# MCU.net
KiCad netlist of a schematic drawn in Altium Designer
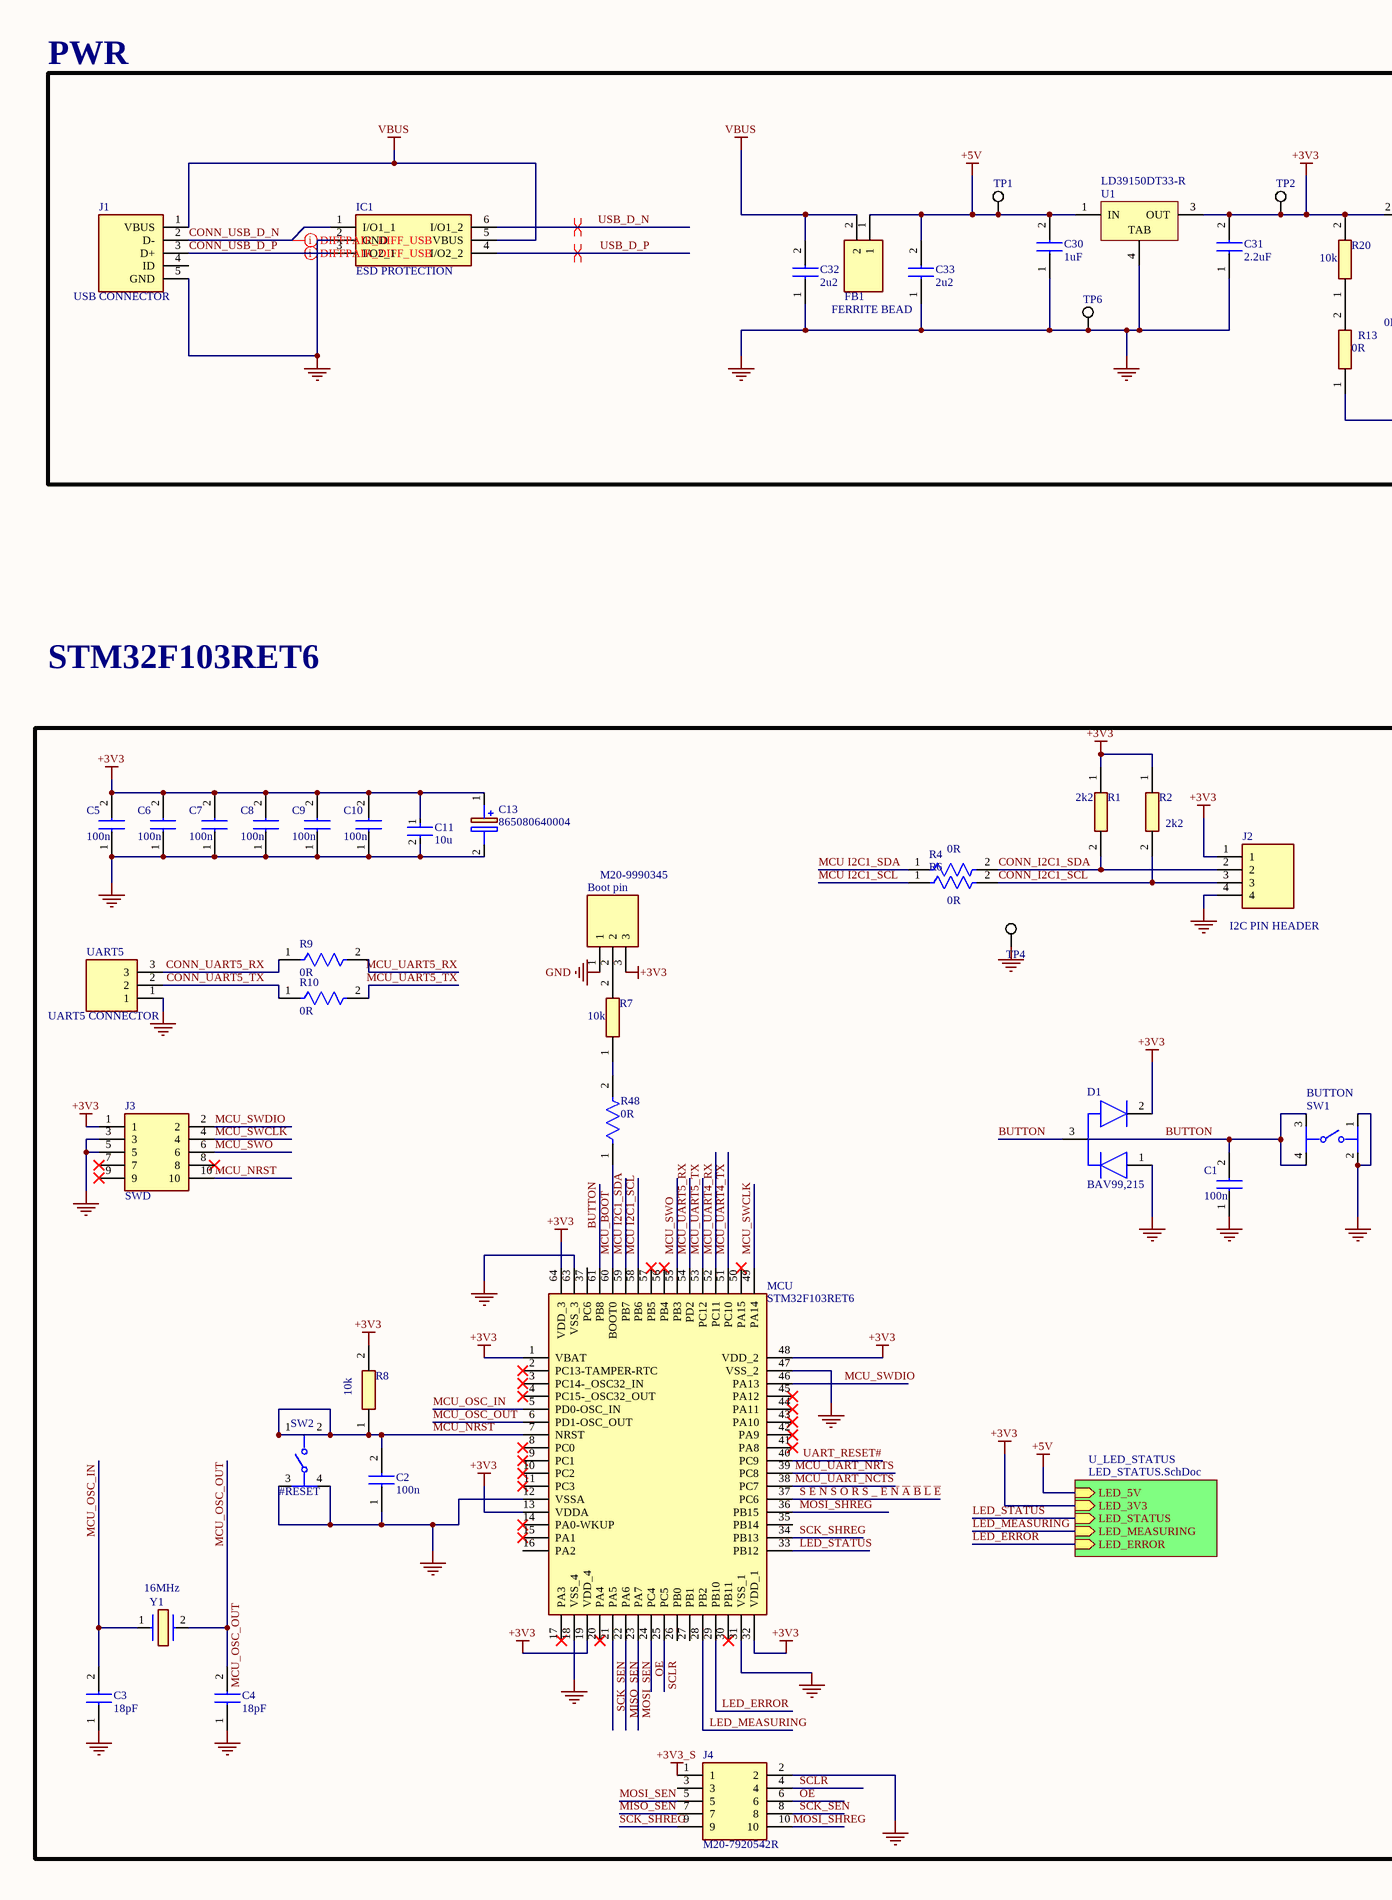
[diagram p0: MCU.SchDoc, left]
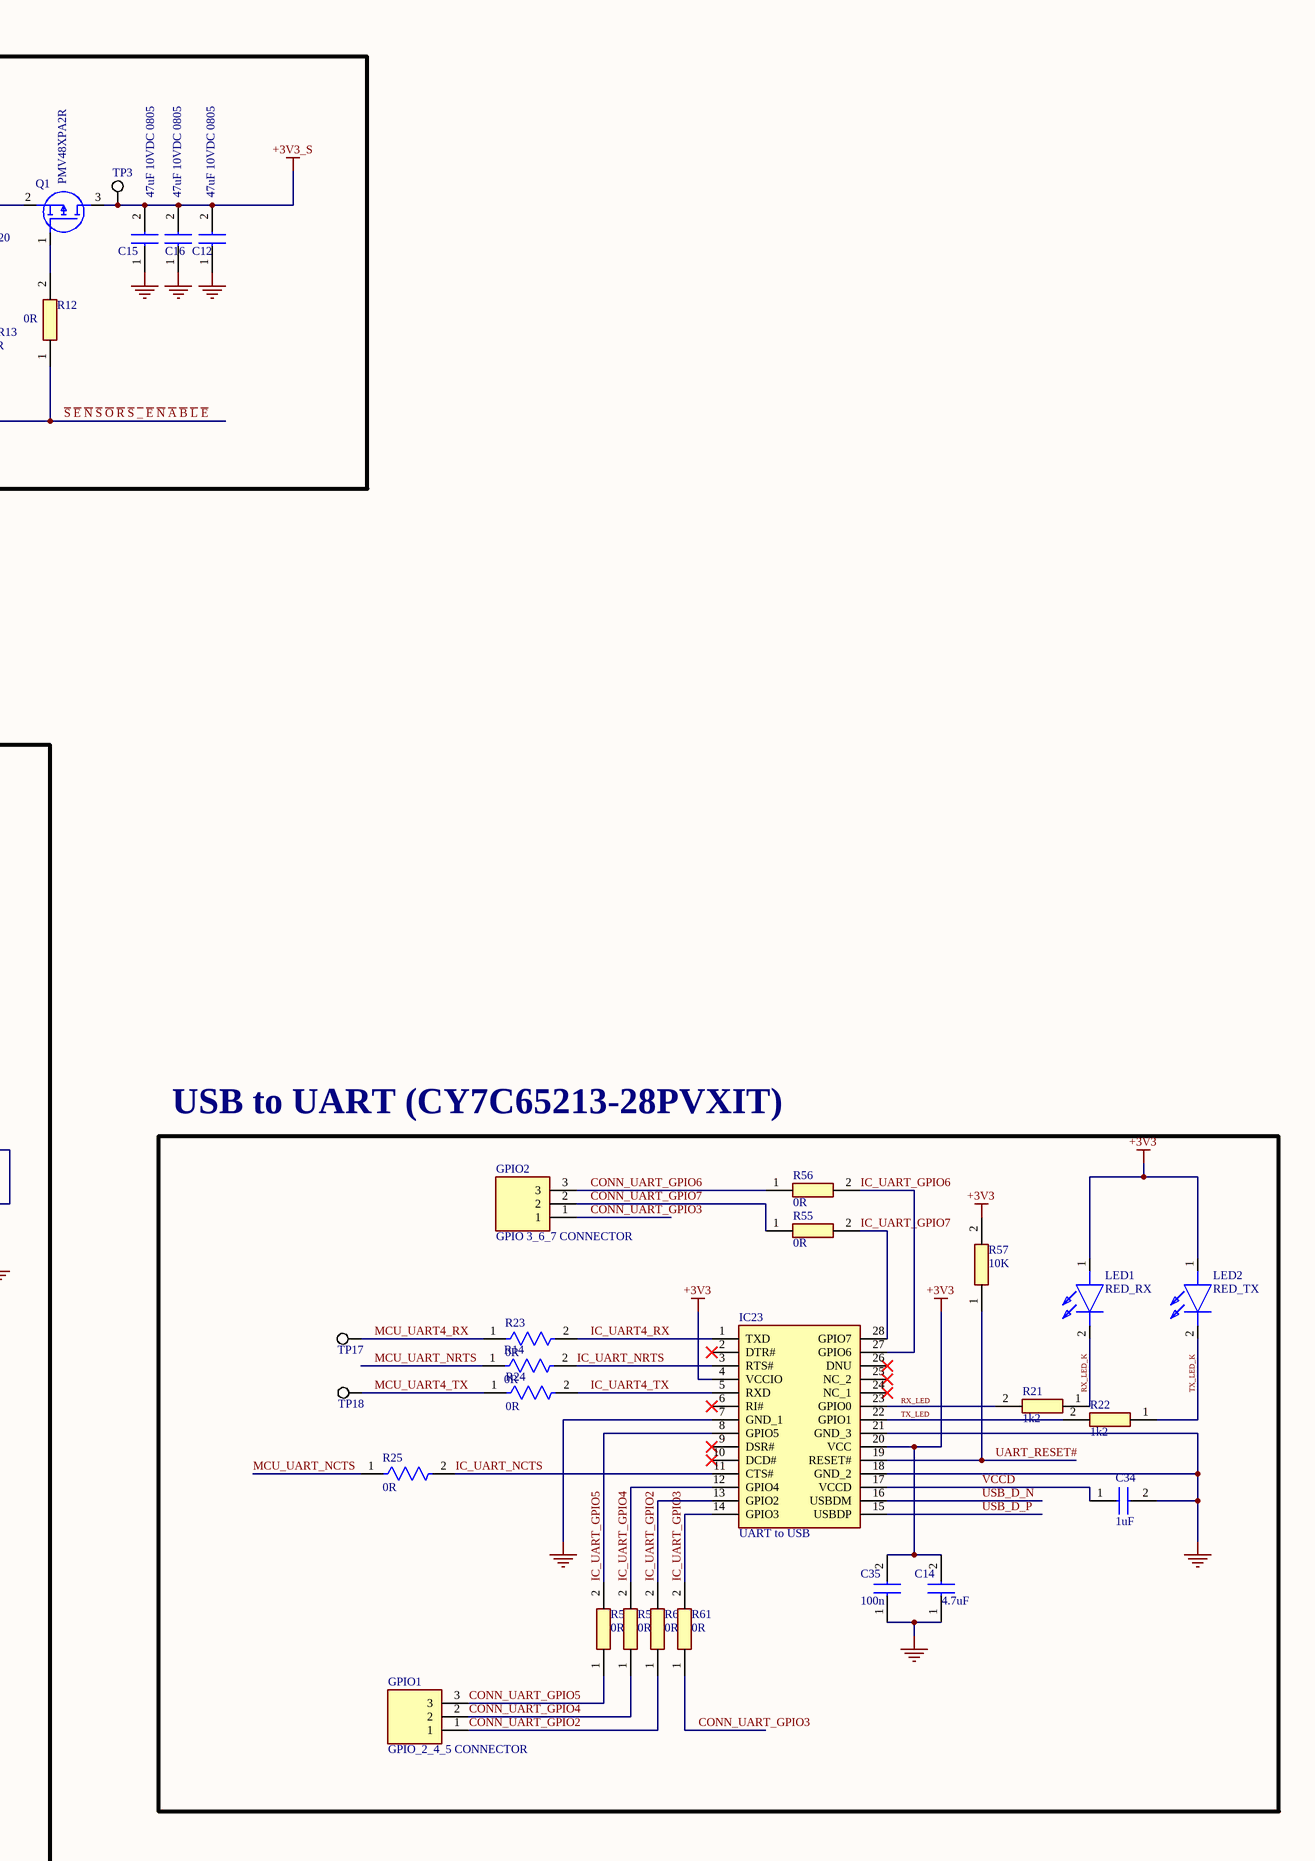
[diagram p1: MCU.SchDoc, right]

(export (version "E")
  (design (tool "Eeschema 10.0.6"))
  (components
    (comp (ref "Boot pin")
      (value "M20-9990345")
      (footprint "SamacSys:HDRV3W64P0X254_1X3_762X254X864P")
      (description "Connector")
      (fields (field (name "MOUSER PART NUMBER") "855-M20-9990345"))
      (libsource (lib "SamacSys") (part "M20-9990345"))
    )
    (comp (ref "C1")
      (value "100n")
      (footprint "SamacSys:CAPC1608X95N")
      (description "Capacitor")
      (fields
        (field (name "MANUFACTURER_PART_NUMBER") "C0603C104J4RAC")
        (field (name "MOUSER PART NUMBER") "80-C0603C104J4RAC")
      )
      (libsource (lib "SamacSys") (part "C0603C104J4RAC"))
    )
    (comp (ref "C2")
      (value "100n")
      (footprint "SamacSys:CAPC1608X90N")
      (description "Capacitor")
      (fields
        (field (name "MANUFACTURER_PART_NUMBER") "CL10A105KA8NFNC")
        (field (name "MOUSER PART NUMBER") "187-CL10A105KA8NFNC")
      )
      (libsource (lib "*") (part "CL10A105KA8NFNC"))
    )
    (comp (ref "C3")
      (value "18pF")
      (footprint "SamacSys:C0603")
      (description "Capacitor")
      (fields
        (field (name "MANUFACTURER_PART_NUMBER") "C0603C180K4HACTU")
        (field (name "MOUSER PART NUMBER") "80-C0603C180K4HACTU")
      )
      (libsource (lib "*") (part "C0603C180K4HACTU"))
    )
    (comp (ref "C4")
      (value "18pF")
      (footprint "SamacSys:C0603")
      (description "Capacitor")
      (fields
        (field (name "MANUFACTURER_PART_NUMBER") "C0603C180K4HACTU")
        (field (name "MOUSER PART NUMBER") "80-C0603C180K4HACTU")
      )
      (libsource (lib "*") (part "C0603C180K4HACTU"))
    )
    (comp (ref "C5")
      (value "100n")
      (footprint "SamacSys:CAPC1608X95N")
      (description "Capacitor")
      (fields
        (field (name "MANUFACTURER_PART_NUMBER") "C0603C104J4RAC")
        (field (name "MOUSER PART NUMBER") "80-C0603C104J4RAC")
      )
      (libsource (lib "SamacSys") (part "C0603C104J4RAC"))
    )
    (comp (ref "C6")
      (value "100n")
      (footprint "SamacSys:CAPC1608X95N")
      (description "Capacitor")
      (fields
        (field (name "MANUFACTURER_PART_NUMBER") "C0603C104J4RAC")
        (field (name "MOUSER PART NUMBER") "80-C0603C104J4RAC")
      )
      (libsource (lib "SamacSys") (part "C0603C104J4RAC"))
    )
    (comp (ref "C7")
      (value "100n")
      (footprint "SamacSys:CAPC1608X95N")
      (description "Capacitor")
      (fields
        (field (name "MANUFACTURER_PART_NUMBER") "C0603C104J4RAC")
        (field (name "MOUSER PART NUMBER") "80-C0603C104J4RAC")
      )
      (libsource (lib "SamacSys") (part "C0603C104J4RAC"))
    )
    (comp (ref "C8")
      (value "100n")
      (footprint "SamacSys:CAPC1608X95N")
      (description "Capacitor")
      (fields
        (field (name "MANUFACTURER_PART_NUMBER") "C0603C104J4RAC")
        (field (name "MOUSER PART NUMBER") "80-C0603C104J4RAC")
      )
      (libsource (lib "SamacSys") (part "C0603C104J4RAC"))
    )
    (comp (ref "C9")
      (value "100n")
      (footprint "SamacSys:CAPC1608X95N")
      (description "Capacitor")
      (fields
        (field (name "MANUFACTURER_PART_NUMBER") "C0603C104J4RAC")
        (field (name "MOUSER PART NUMBER") "80-C0603C104J4RAC")
      )
      (libsource (lib "SamacSys") (part "C0603C104J4RAC"))
    )
    (comp (ref "C10")
      (value "100n")
      (footprint "SamacSys:CAPC1608X95N")
      (description "Capacitor")
      (fields
        (field (name "MANUFACTURER_PART_NUMBER") "C0603C104J4RAC")
        (field (name "MOUSER PART NUMBER") "80-C0603C104J4RAC")
      )
      (libsource (lib "SamacSys") (part "C0603C104J4RAC"))
    )
    (comp (ref "C11")
      (value "10u")
      (footprint "FP-GRM188-0_2-IPC_A")
      (description "Chip Multilayer Ceramic Capacitors for General Purpose, 0603, 10uF, X5R, 15%, 20%, 16V")
      (fields (field (name "TOLERANCE") "20%") (field (name "VOLTAGE") "16V"))
      (libsource (lib "Altium Content Vault") (part "11868f565c42a9108669ba33697ecf6"))
    )
    (comp (ref "C12")
      (value "47uF 10VDC 0805")
      (footprint "SamacSys:CAPC2012X145N")
      (description "Capacitor")
      (fields
        (field (name "MANUFACTURER_PART_NUMBER") "GRM21BR61A476ME15K")
        (field (name "MOUSER PART NUMBER") "81-GRM21BR61A476ME5K")
      )
      (libsource (lib "*") (part "GRM21BR61A476ME15K"))
    )
    (comp (ref "C13")
      (value "865080640004")
      (footprint "SamacSys:865080640004")
      (description "Capacitor Polarised")
      (fields (field (name "MOUSER PART NUMBER") "710-865080640004"))
      (libsource (lib "SamacSys") (part "865080640004"))
    )
    (comp (ref "C14")
      (value "4.7uF")
      (footprint "SamacSys:CAPC1608X95N")
      (description "Capacitor")
      (fields
        (field (name "MANUFACTURER_PART_NUMBER") "C0603C104J4RAC")
        (field (name "MOUSER PART NUMBER") "80-C0603C104J4RAC")
      )
      (libsource (lib "SamacSys") (part "C0603C104J4RAC"))
    )
    (comp (ref "C15")
      (value "47uF 10VDC 0805")
      (footprint "SamacSys:CAPC2012X145N")
      (description "Capacitor")
      (fields
        (field (name "MANUFACTURER_PART_NUMBER") "GRM21BR61A476ME15K")
        (field (name "MOUSER PART NUMBER") "81-GRM21BR61A476ME5K")
      )
      (libsource (lib "*") (part "GRM21BR61A476ME15K"))
    )
    (comp (ref "C16")
      (value "47uF 10VDC 0805")
      (footprint "SamacSys:CAPC2012X145N")
      (description "Capacitor")
      (fields
        (field (name "MANUFACTURER_PART_NUMBER") "GRM21BR61A476ME15K")
        (field (name "MOUSER PART NUMBER") "81-GRM21BR61A476ME5K")
      )
      (libsource (lib "*") (part "GRM21BR61A476ME15K"))
    )
    (comp (ref "C30")
      (value "1uF")
      (footprint "SamacSys:CAPC1608X90N")
      (description "Capacitor")
      (fields
        (field (name "MANUFACTURER_PART_NUMBER") "CL10A105KA8NFNC")
        (field (name "MOUSER PART NUMBER") "187-CL10A105KA8NFNC")
      )
      (libsource (lib "*") (part "CL10A105KA8NFNC"))
    )
    (comp (ref "C31")
      (value "2.2uF")
      (footprint "SamacSys:CAPC1608X90N")
      (description "Capacitor")
      (fields
        (field (name "MANUFACTURER_PART_NUMBER") "CL10A105KA8NFNC")
        (field (name "MOUSER PART NUMBER") "187-CL10A105KA8NFNC")
      )
      (libsource (lib "*") (part "CL10A105KA8NFNC"))
    )
    (comp (ref "C32")
      (value "2u2")
      (footprint "SamacSys:CAPC1608X90N")
      (description "Capacitor")
      (fields
        (field (name "MANUFACTURER_PART_NUMBER") "CL10A105KA8NFNC")
        (field (name "MOUSER PART NUMBER") "187-CL10A105KA8NFNC")
      )
      (libsource (lib "*") (part "CL10A105KA8NFNC"))
    )
    (comp (ref "C33")
      (value "2u2")
      (footprint "SamacSys:CAPC1608X90N")
      (description "Capacitor")
      (fields
        (field (name "MANUFACTURER_PART_NUMBER") "CL10A105KA8NFNC")
        (field (name "MOUSER PART NUMBER") "187-CL10A105KA8NFNC")
      )
      (libsource (lib "*") (part "CL10A105KA8NFNC"))
    )
    (comp (ref "C34")
      (value "1uF")
      (footprint "SamacSys:CAPC1608X90N")
      (description "Capacitor")
      (fields
        (field (name "MANUFACTURER_PART_NUMBER") "CL10A105KA8NFNC")
        (field (name "MOUSER PART NUMBER") "187-CL10A105KA8NFNC")
      )
      (libsource (lib "SamacSys") (part "CL10A105KA8NFNC"))
    )
    (comp (ref "C35")
      (value "100n")
      (footprint "SamacSys:CAPC1608X95N")
      (description "Capacitor")
      (fields
        (field (name "MANUFACTURER_PART_NUMBER") "C0603C104J4RAC")
        (field (name "MOUSER PART NUMBER") "80-C0603C104J4RAC")
      )
      (libsource (lib "SamacSys") (part "C0603C104J4RAC"))
    )
    (comp (ref "D1")
      (value "BAV99,215")
      (footprint "SamacSys:BAV99215")
      (description "Diode")
      (fields (field (name "MOUSER PART NUMBER") "771-BAV99-T/R"))
      (libsource (lib "*") (part "BAV99,215"))
    )
    (comp (ref "FB1")
      (value "FERRITE BEAD")
      (footprint "SamacSys:BEADC1608X75N")
      (description "Ferrite Bead")
      (fields
        (field (name "MANUFACTURER_PART_NUMBER") "BLM18KN101EH1D")
        (field (name "MOUSER PART NUMBER") "81-BLM18KN101EH1D")
      )
      (libsource (lib "SamacSys") (part "BLM18KN101EH1D"))
    )
    (comp (ref "GPIO1")
      (value "GPIO_2_4_5 CONNECTOR")
      (footprint "SamacSys:HDRV3W64P0X254_1X3_762X254X864P")
      (description "Connector")
      (fields
        (field (name "MANUFACTURER_PART_NUMBER") "M20-9990345")
        (field (name "MOUSER PART NUMBER") "855-M20-9990345")
      )
      (libsource (lib "") (part "M20-9990345_1"))
    )
    (comp (ref "GPIO2")
      (value "GPIO 3_6_7 CONNECTOR")
      (footprint "SamacSys:HDRV3W64P0X254_1X3_762X254X864P")
      (description "Connector")
      (fields
        (field (name "MANUFACTURER_PART_NUMBER") "M20-9990345")
        (field (name "MOUSER PART NUMBER") "855-M20-9990345")
      )
      (libsource (lib "") (part "M20-9990345_1"))
    )
    (comp (ref "IC1")
      (value "ESD PROTECTION")
      (footprint "SamacSys:SOT95P280X145-6N")
      (description "Integrated Circuit")
      (fields
        (field (name "MANUFACTURER_PART_NUMBER") "USBLC6-2SC6")
        (field (name "MOUSER PART NUMBER") "511-USBLC6-2SC6")
      )
      (libsource (lib "*") (part "USBLC6-2SC6"))
    )
    (comp (ref "IC23")
      (value "UART to USB")
      (footprint "SamacSys:SOP65P780X200-28N")
      (description "Integrated Circuit")
      (fields
        (field (name "MANUFACTURER_PART_NUMBER") "CY7C65213-28PVXIT")
        (field (name "MOUSER PART NUMBER") "727-CY7C6521328PVXIT")
      )
      (libsource (lib "*") (part "CY7C65213-28PVXIT"))
    )
    (comp (ref "J1")
      (value "USB CONNECTOR")
      (footprint "SamacSys:47346-0001")
      (description "Connector")
      (fields
        (field (name "MANUFACTURER_PART_NUMBER") "47346-0001")
        (field (name "MOUSER PART NUMBER") "538-47346-0001")
      )
      (libsource (lib "*") (part "47346-0001"))
    )
    (comp (ref "J2")
      (value "I2C PIN HEADER")
      (footprint "SamacSys:HDRV4W90P0X254_1X4_994X249X560P")
      (description "Connector")
      (fields
        (field (name "MANUFACTURER_PART_NUMBER") "90120-0764")
        (field (name "MOUSER PART NUMBER") "538-90120-0764")
      )
      (libsource (lib "SamacSys") (part "90120-0764"))
    )
    (comp (ref "J3")
      (value "SWD")
      (footprint "SamacSys:HDRV10W64P254_2X5_1270X508X834P")
      (description "Connector")
      (fields
        (field (name "MANUFACTURER_PART_NUMBER") "M20-9760542")
        (field (name "MOUSER PART NUMBER") "855-M20-9760542")
      )
      (libsource (lib "SamacSys") (part "M20-9760542"))
    )
    (comp (ref "J4")
      (value "M20-7920542R")
      (footprint "SamacSys:M207920542R")
      (description "Connector")
      (fields (field (name "MOUSER PART NUMBER") "855-M20-7920542R"))
      (libsource (lib "SamacSys") (part "M20-7920542R"))
    )
    (comp (ref "LED1")
      (value "RED_RX")
      (footprint "SamacSys:APT2012SECKJ3PRV")
      (description "LED")
      (fields
        (field (name "MANUFACTURER_PART_NUMBER") "APT2012SECK/J3-PRV")
        (field (name "MOUSER PART NUMBER") "604-APT2012SECKJ3PRV")
      )
      (libsource (lib "*") (part "APT2012SECK_J3-PRV"))
    )
    (comp (ref "LED2")
      (value "RED_TX")
      (footprint "SamacSys:APT2012SECKJ3PRV")
      (description "LED")
      (fields
        (field (name "MANUFACTURER_PART_NUMBER") "APT2012SECK/J3-PRV")
        (field (name "MOUSER PART NUMBER") "604-APT2012SECKJ3PRV")
      )
      (libsource (lib "*") (part "APT2012SECK_J3-PRV"))
    )
    (comp (ref "MCU")
      (value "STM32F103RET6")
      (footprint "SamacSys:QFP50P1200X1200X160-64N")
      (description "Integrated Circuit")
      (fields (field (name "MOUSER PART NUMBER") "511-STM32F103RET6"))
      (libsource (lib "*") (part "STM32F103RET6"))
    )
    (comp (ref "Q1")
      (value "PMV48XPA2R")
      (footprint "SamacSys:SOT95P230X110-3N")
      (description "MOSFET (P-Channel)")
      (fields (field (name "MOUSER PART NUMBER") "771-PMV48XPA2R"))
      (libsource (lib "*") (part "PMV48XPA2R"))
    )
    (comp (ref "R1")
      (value "2k2")
      (footprint "SamacSys:RESC1608X55N")
      (description "Resistor")
      (fields
        (field (name "MANUFACTURER_PART_NUMBER") "RK73B1JTTD103J")
        (field (name "MOUSER PART NUMBER") "660-RK73B1JTTD103J")
      )
      (libsource (lib "") (part "RK73B1JTTD103J_2"))
    )
    (comp (ref "R2")
      (value "2k2")
      (footprint "SamacSys:RESC1608X55N")
      (description "Resistor")
      (fields
        (field (name "MANUFACTURER_PART_NUMBER") "RK73B1JTTD103J")
        (field (name "MOUSER PART NUMBER") "660-RK73B1JTTD103J")
      )
      (libsource (lib "") (part "RK73B1JTTD103J_2"))
    )
    (comp (ref "R4")
      (value "0R")
      (footprint "FP-ERJ-3GEY0R00V-MFG")
      (description "RES SMD 0 OHM JUMPER 1/10W 0603")
      (fields (field (name "TOLERANCE") "5%") (field (name "MANUFACTURER PART NUMBER") "ERJ-3GEY0R00V"))
      (libsource (lib "Altium Content Vault") (part "1029c3af85768c4190bb7ad29bc67b5"))
    )
    (comp (ref "R6")
      (value "0R")
      (footprint "FP-ERJ-3GEY0R00V-MFG")
      (description "RES SMD 0 OHM JUMPER 1/10W 0603")
      (fields (field (name "TOLERANCE") "5%") (field (name "MANUFACTURER PART NUMBER") "ERJ-3GEY0R00V"))
      (libsource (lib "Altium Content Vault") (part "1029c3af85768c4190bb7ad29bc67b5"))
    )
    (comp (ref "R7")
      (value "10k")
      (footprint "SamacSys:RESC1608X55N")
      (description "Resistor")
      (fields
        (field (name "MANUFACTURER_PART_NUMBER") "RK73B1JTTD103J")
        (field (name "MOUSER PART NUMBER") "660-RK73B1JTTD103J")
      )
      (libsource (lib "*") (part "RK73B1JTTD103J"))
    )
    (comp (ref "R8")
      (value "10k")
      (footprint "SamacSys:RESC1608X55N")
      (description "Resistor")
      (fields
        (field (name "MANUFACTURER_PART_NUMBER") "RK73B1JTTD103J")
        (field (name "MOUSER PART NUMBER") "660-RK73B1JTTD103J")
      )
      (libsource (lib "*") (part "RK73B1JTTD103J"))
    )
    (comp (ref "R9")
      (value "0R")
      (footprint "FP-ERJ-3GEY0R00V-MFG")
      (description "RES SMD 0 OHM JUMPER 1/10W 0603")
      (fields (field (name "TOLERANCE") "5%") (field (name "MANUFACTURER PART NUMBER") "ERJ-3GEY0R00V"))
      (libsource (lib "Altium Content Vault") (part "1029c3af85768c4190bb7ad29bc67b5"))
    )
    (comp (ref "R10")
      (value "0R")
      (footprint "FP-ERJ-3GEY0R00V-MFG")
      (description "RES SMD 0 OHM JUMPER 1/10W 0603")
      (fields (field (name "TOLERANCE") "5%") (field (name "MANUFACTURER PART NUMBER") "ERJ-3GEY0R00V"))
      (libsource (lib "Altium Content Vault") (part "1029c3af85768c4190bb7ad29bc67b5"))
    )
    (comp (ref "R12")
      (value "0R")
      (footprint "SamacSys:RESC1608X55N")
      (description "Resistor")
      (fields
        (field (name "MANUFACTURER_PART_NUMBER") "RK73B1JTTD103J")
        (field (name "MOUSER PART NUMBER") "660-RK73B1JTTD103J")
      )
      (libsource (lib "*") (part "RK73B1JTTD103J"))
    )
    (comp (ref "R13")
      (value "0R")
      (footprint "SamacSys:RESC1608X55N")
      (description "Resistor")
      (fields
        (field (name "MANUFACTURER_PART_NUMBER") "RK73B1JTTD103J")
        (field (name "MOUSER PART NUMBER") "660-RK73B1JTTD103J")
      )
      (libsource (lib "*") (part "RK73B1JTTD103J"))
    )
    (comp (ref "R14")
      (value "0R")
      (footprint "FP-ERJ-3GEY0R00V-MFG")
      (description "RES SMD 0 OHM JUMPER 1/10W 0603")
      (fields (field (name "TOLERANCE") "5%") (field (name "MANUFACTURER PART NUMBER") "ERJ-3GEY0R00V"))
      (libsource (lib "Altium Content Vault") (part "1029c3af85768c4190bb7ad29bc67b5"))
    )
    (comp (ref "R20")
      (value "10k")
      (footprint "SamacSys:RESC1608X55N")
      (description "Resistor")
      (fields
        (field (name "MANUFACTURER_PART_NUMBER") "RK73B1JTTD103J")
        (field (name "MOUSER PART NUMBER") "660-RK73B1JTTD103J")
      )
      (libsource (lib "*") (part "RK73B1JTTD103J"))
    )
    (comp (ref "R21")
      (value "1k2")
      (footprint "SamacSys:RESC1608X55N")
      (description "Resistor")
      (fields
        (field (name "MANUFACTURER_PART_NUMBER") "RK73B1JTTD103J")
        (field (name "MOUSER PART NUMBER") "660-RK73B1JTTD103J")
      )
      (libsource (lib "") (part "RK73B1JTTD103J_3"))
    )
    (comp (ref "R22")
      (value "1k2")
      (footprint "SamacSys:RESC1608X55N")
      (description "Resistor")
      (fields
        (field (name "MANUFACTURER_PART_NUMBER") "RK73B1JTTD103J")
        (field (name "MOUSER PART NUMBER") "660-RK73B1JTTD103J")
      )
      (libsource (lib "") (part "RK73B1JTTD103J_3"))
    )
    (comp (ref "R23")
      (value "0R")
      (footprint "FP-ERJ-3GEY0R00V-MFG")
      (description "RES SMD 0 OHM JUMPER 1/10W 0603")
      (fields (field (name "TOLERANCE") "5%") (field (name "MANUFACTURER PART NUMBER") "ERJ-3GEY0R00V"))
      (libsource (lib "Altium Content Vault") (part "1029c3af85768c4190bb7ad29bc67b5"))
    )
    (comp (ref "R24")
      (value "0R")
      (footprint "FP-ERJ-3GEY0R00V-MFG")
      (description "RES SMD 0 OHM JUMPER 1/10W 0603")
      (fields (field (name "TOLERANCE") "5%") (field (name "MANUFACTURER PART NUMBER") "ERJ-3GEY0R00V"))
      (libsource (lib "Altium Content Vault") (part "1029c3af85768c4190bb7ad29bc67b5"))
    )
    (comp (ref "R25")
      (value "0R")
      (footprint "FP-ERJ-3GEY0R00V-MFG")
      (description "RES SMD 0 OHM JUMPER 1/10W 0603")
      (fields (field (name "TOLERANCE") "5%") (field (name "MANUFACTURER PART NUMBER") "ERJ-3GEY0R00V"))
      (libsource (lib "Altium Content Vault") (part "1029c3af85768c4190bb7ad29bc67b5"))
    )
    (comp (ref "R48")
      (value "0R")
      (footprint "FP-ERJ-3GEY0R00V-MFG")
      (description "RES SMD 0 OHM JUMPER 1/10W 0603")
      (fields (field (name "TOLERANCE") "5%") (field (name "MANUFACTURER PART NUMBER") "ERJ-3GEY0R00V"))
      (libsource (lib "Altium Content Vault") (part "1029c3af85768c4190bb7ad29bc67b5"))
    )
    (comp (ref "R55")
      (value "0R")
      (footprint "SamacSys:RESC1608X55N")
      (description "Resistor")
      (fields
        (field (name "MANUFACTURER_PART_NUMBER") "RK73B1JTTD103J")
        (field (name "MOUSER PART NUMBER") "660-RK73B1JTTD103J")
      )
      (libsource (lib "") (part "RK73B1JTTD103J_1"))
    )
    (comp (ref "R56")
      (value "0R")
      (footprint "SamacSys:RESC1608X55N")
      (description "Resistor")
      (fields
        (field (name "MANUFACTURER_PART_NUMBER") "RK73B1JTTD103J")
        (field (name "MOUSER PART NUMBER") "660-RK73B1JTTD103J")
      )
      (libsource (lib "") (part "RK73B1JTTD103J_1"))
    )
    (comp (ref "R57")
      (value "10K")
      (footprint "SamacSys:RESC1608X55N")
      (description "Resistor")
      (fields
        (field (name "MANUFACTURER_PART_NUMBER") "RK73B1JTTD103J")
        (field (name "MOUSER PART NUMBER") "660-RK73B1JTTD103J")
      )
      (libsource (lib "*") (part "RK73B1JTTD103J"))
    )
    (comp (ref "R58")
      (value "0R")
      (footprint "SamacSys:RESC1608X55N")
      (description "Resistor")
      (fields
        (field (name "MANUFACTURER_PART_NUMBER") "RK73B1JTTD103J")
        (field (name "MOUSER PART NUMBER") "660-RK73B1JTTD103J")
      )
      (libsource (lib "*") (part "RK73B1JTTD103J"))
    )
    (comp (ref "R59")
      (value "0R")
      (footprint "SamacSys:RESC1608X55N")
      (description "Resistor")
      (fields
        (field (name "MANUFACTURER_PART_NUMBER") "RK73B1JTTD103J")
        (field (name "MOUSER PART NUMBER") "660-RK73B1JTTD103J")
      )
      (libsource (lib "*") (part "RK73B1JTTD103J"))
    )
    (comp (ref "R60")
      (value "0R")
      (footprint "SamacSys:RESC1608X55N")
      (description "Resistor")
      (fields
        (field (name "MANUFACTURER_PART_NUMBER") "RK73B1JTTD103J")
        (field (name "MOUSER PART NUMBER") "660-RK73B1JTTD103J")
      )
      (libsource (lib "*") (part "RK73B1JTTD103J"))
    )
    (comp (ref "R61")
      (value "0R")
      (footprint "SamacSys:RESC1608X55N")
      (description "Resistor")
      (fields
        (field (name "MANUFACTURER_PART_NUMBER") "RK73B1JTTD103J")
        (field (name "MOUSER PART NUMBER") "660-RK73B1JTTD103J")
      )
      (libsource (lib "*") (part "RK73B1JTTD103J"))
    )
    (comp (ref "SW1")
      (value "BUTTON")
      (footprint "FP-PTS645SM43SMTR92LFS-MFG")
      (description "SWITCH TACTILE SPST-NO 0.05A 12V")
      (libsource (lib "Altium Content Vault") (part "1adf0dd01260c80cf25a44bfd6b99ba"))
    )
    (comp (ref "SW2")
      (value "#RESET")
      (footprint "FP-PTS645SM43SMTR92LFS-MFG")
      (description "SWITCH TACTILE SPST-NO 0.05A 12V")
      (libsource (lib "Altium Content Vault") (part "1adf0dd01260c80cf25a44bfd6b99ba"))
    )
    (comp (ref "TP1")
      (value "5019")
      (footprint "KSTN-5019_V")
      (description "Test Point, 1 Position SMD, RoHS, Tape and Reel")
      (libsource (lib "Altium Content Vault") (part "TESTPOINT_WHITE"))
    )
    (comp (ref "TP2")
      (value "5019")
      (footprint "KSTN-5019_V")
      (description "Test Point, 1 Position SMD, RoHS, Tape and Reel")
      (libsource (lib "Altium Content Vault") (part "TESTPOINT_WHITE"))
    )
    (comp (ref "TP3")
      (value "5019")
      (footprint "KSTN-5019_V")
      (description "Test Point, 1 Position SMD, RoHS, Tape and Reel")
      (libsource (lib "Altium Content Vault") (part "TESTPOINT_WHITE"))
    )
    (comp (ref "TP4")
      (value "5019")
      (footprint "KSTN-5019_V")
      (description "Test Point, 1 Position SMD, RoHS, Tape and Reel")
      (libsource (lib "Altium Content Vault") (part "TESTPOINT_WHITE"))
    )
    (comp (ref "TP6")
      (value "5019")
      (footprint "KSTN-5019_V")
      (description "Test Point, 1 Position SMD, RoHS, Tape and Reel")
      (libsource (lib "Altium Content Vault") (part "TESTPOINT_WHITE"))
    )
    (comp (ref "TP17")
      (value "5019")
      (footprint "KSTN-5019_V")
      (description "Test Point, 1 Position SMD, RoHS, Tape and Reel")
      (libsource (lib "Altium Content Vault") (part "TESTPOINT_WHITE"))
    )
    (comp (ref "TP18")
      (value "5019")
      (footprint "KSTN-5019_V")
      (description "Test Point, 1 Position SMD, RoHS, Tape and Reel")
      (libsource (lib "Altium Content Vault") (part "TESTPOINT_WHITE"))
    )
    (comp (ref "U1")
      (value "LD39150DT33-R")
      (footprint "TO-252_M")
      (description "Ultra Low Drop BICMOS Voltage Regulator, 3.3V, 3-Pin DPAK, Tape and Reel")
      (libsource (lib "Altium Content Vault") (part "PM-REG-LD29150-SOT3"))
    )
    (comp (ref "UART5")
      (value "UART5 CONNECTOR")
      (footprint "SamacSys:HDRV3W64P0X254_1X3_762X254X864P")
      (description "Connector")
      (fields
        (field (name "MANUFACTURER_PART_NUMBER") "M20-9990345")
        (field (name "MOUSER PART NUMBER") "855-M20-9990345")
      )
      (libsource (lib "") (part "M20-9990345_1"))
    )
    (comp (ref "Y1")
      (value "16MHz")
      (footprint "SamacSys:ABLS")
      (description "Crystal or Oscillator")
      (fields
        (field (name "MANUFACTURER_PART_NUMBER") "ABLS-16.000MHZ-B2-T")
        (field (name "MOUSER PART NUMBER") "815-ABLS-16-B2")
      )
      (libsource (lib "SamacSys") (part "ABLS-16.000MHZ-B2-T"))
    )
  )
  (nets
    (net (code "1") (name "+3V3") (class "Default")
      (node (ref "Boot pin") (pin "3") (pinfunction "3_3") (pintype "passive"))
      (node (ref "C10") (pin "2") (pinfunction "2_2") (pintype "passive"))
      (node (ref "C11") (pin "1") (pinfunction "1_1") (pintype "passive"))
      (node (ref "C13") (pin "1") (pinfunction "+_1") (pintype "passive"))
      (node (ref "C14") (pin "2") (pinfunction "2_2") (pintype "passive"))
      (node (ref "C31") (pin "2") (pinfunction "2_2") (pintype "passive"))
      (node (ref "C35") (pin "2") (pinfunction "2_2") (pintype "passive"))
      (node (ref "C5") (pin "2") (pinfunction "2_2") (pintype "passive"))
      (node (ref "C6") (pin "2") (pinfunction "2_2") (pintype "passive"))
      (node (ref "C7") (pin "2") (pinfunction "2_2") (pintype "passive"))
      (node (ref "C8") (pin "2") (pinfunction "2_2") (pintype "passive"))
      (node (ref "C9") (pin "2") (pinfunction "2_2") (pintype "passive"))
      (node (ref "D1") (pin "2") (pinfunction "E_2") (pintype "passive"))
      (node (ref "IC23") (pin "20") (pinfunction "VCC_20") (pintype "passive"))
      (node (ref "IC23") (pin "4") (pinfunction "VCCIO_4") (pintype "passive"))
      (node (ref "J2") (pin "1") (pinfunction "1_1") (pintype "passive"))
      (node (ref "J3") (pin "1") (pinfunction "1_1") (pintype "passive"))
      (node (ref "LED1") (pin "1") (pinfunction "A_1") (pintype "passive"))
      (node (ref "LED2") (pin "1") (pinfunction "A_1") (pintype "passive"))
      (node (ref "MCU") (pin "1") (pinfunction "VBAT_1") (pintype "passive"))
      (node (ref "MCU") (pin "13") (pinfunction "VDDA_13") (pintype "passive"))
      (node (ref "MCU") (pin "19") (pinfunction "VDD_4_19") (pintype "passive"))
      (node (ref "MCU") (pin "32") (pinfunction "VDD_1_32") (pintype "passive"))
      (node (ref "MCU") (pin "48") (pinfunction "VDD_2_48") (pintype "passive"))
      (node (ref "MCU") (pin "64") (pinfunction "VDD_3_64") (pintype "passive"))
      (node (ref "Q1") (pin "2") (pinfunction "S_2") (pintype "passive"))
      (node (ref "R1") (pin "1") (pinfunction "1_1") (pintype "passive"))
      (node (ref "R2") (pin "1") (pinfunction "1_1") (pintype "passive"))
      (node (ref "R20") (pin "2") (pinfunction "2_2") (pintype "passive"))
      (node (ref "R57") (pin "2") (pinfunction "2_2") (pintype "passive"))
      (node (ref "R8") (pin "2") (pinfunction "2_2") (pintype "passive"))
      (node (ref "TP2") (pin "1") (pinfunction "1_1") (pintype "passive"))
      (node (ref "U1") (pin "3") (pinfunction "OUT_3") (pintype "power_in"))
    )
    (net (code "2") (name "+3V3_S") (class "Default")
      (node (ref "C12") (pin "2") (pinfunction "2_2") (pintype "passive"))
      (node (ref "C15") (pin "2") (pinfunction "2_2") (pintype "passive"))
      (node (ref "C16") (pin "2") (pinfunction "2_2") (pintype "passive"))
      (node (ref "J4") (pin "1") (pinfunction "1_1") (pintype "passive"))
      (node (ref "Q1") (pin "3") (pinfunction "D_3") (pintype "passive"))
      (node (ref "TP3") (pin "1") (pinfunction "1_1") (pintype "passive"))
    )
    (net (code "3") (name "+5V") (class "Default")
      (node (ref "C30") (pin "2") (pinfunction "2_2") (pintype "passive"))
      (node (ref "C33") (pin "2") (pinfunction "2_2") (pintype "passive"))
      (node (ref "FB1") (pin "1") (pinfunction "1_1") (pintype "passive"))
      (node (ref "TP1") (pin "1") (pinfunction "1_1") (pintype "passive"))
      (node (ref "U1") (pin "1") (pinfunction "IN_1") (pintype "power_in"))
    )
    (net (code "4") (name "/BUTTON") (class "Default")
      (node (ref "C1") (pin "2") (pinfunction "2_2") (pintype "passive"))
      (node (ref "D1") (pin "3") (pinfunction "C_3") (pintype "passive"))
      (node (ref "MCU") (pin "61") (pinfunction "PB8_61") (pintype "passive"))
      (node (ref "SW1") (pin "3") (pinfunction "3_3") (pintype "passive"))
      (node (ref "SW1") (pin "4") (pinfunction "4_4") (pintype "passive"))
    )
    (net (code "5") (name "/CONN_I2C1_SCL") (class "Default")
      (node (ref "J2") (pin "3") (pinfunction "3_3") (pintype "passive"))
      (node (ref "R2") (pin "2") (pinfunction "2_2") (pintype "passive"))
      (node (ref "R6") (pin "2") (pinfunction "2_2") (pintype "passive"))
    )
    (net (code "6") (name "/CONN_I2C1_SDA") (class "Default")
      (node (ref "J2") (pin "2") (pinfunction "2_2") (pintype "passive"))
      (node (ref "R1") (pin "2") (pinfunction "2_2") (pintype "passive"))
      (node (ref "R4") (pin "2") (pinfunction "2_2") (pintype "passive"))
    )
    (net (code "7") (name "/CONN_UART5_RX") (class "Default")
      (node (ref "R9") (pin "1") (pinfunction "1_1") (pintype "passive"))
      (node (ref "UART5") (pin "3") (pinfunction "3_3") (pintype "passive"))
    )
    (net (code "8") (name "/CONN_UART5_TX") (class "Default")
      (node (ref "R10") (pin "1") (pinfunction "1_1") (pintype "passive"))
      (node (ref "UART5") (pin "2") (pinfunction "2_2") (pintype "passive"))
    )
    (net (code "9") (name "/CONN_UART_GPIO2") (class "Default")
      (node (ref "GPIO1") (pin "1") (pinfunction "1_1") (pintype "passive"))
      (node (ref "R60") (pin "1") (pinfunction "1_1") (pintype "passive"))
    )
    (net (code "10") (name "/CONN_UART_GPIO3") (class "Default")
      (node (ref "GPIO2") (pin "1") (pinfunction "1_1") (pintype "passive"))
      (node (ref "R61") (pin "1") (pinfunction "1_1") (pintype "passive"))
    )
    (net (code "11") (name "/CONN_UART_GPIO4") (class "Default")
      (node (ref "GPIO1") (pin "2") (pinfunction "2_2") (pintype "passive"))
      (node (ref "R59") (pin "1") (pinfunction "1_1") (pintype "passive"))
    )
    (net (code "12") (name "/CONN_UART_GPIO5") (class "Default")
      (node (ref "GPIO1") (pin "3") (pinfunction "3_3") (pintype "passive"))
      (node (ref "R58") (pin "1") (pinfunction "1_1") (pintype "passive"))
    )
    (net (code "13") (name "/CONN_UART_GPIO6") (class "Default")
      (node (ref "GPIO2") (pin "3") (pinfunction "3_3") (pintype "passive"))
      (node (ref "R56") (pin "1") (pinfunction "1_1") (pintype "passive"))
    )
    (net (code "14") (name "/CONN_UART_GPIO7") (class "Default")
      (node (ref "GPIO2") (pin "2") (pinfunction "2_2") (pintype "passive"))
      (node (ref "R55") (pin "1") (pinfunction "1_1") (pintype "passive"))
    )
    (net (code "15") (name "/CONN_USB_D_N") (class "Default")
      (node (ref "IC1") (pin "1") (pinfunction "I/O1_1_1") (pintype "passive"))
      (node (ref "J1") (pin "2") (pinfunction "D-_2") (pintype "passive"))
    )
    (net (code "16") (name "/CONN_USB_D_P") (class "Default")
      (node (ref "IC1") (pin "3") (pinfunction "I/O2_1_3") (pintype "passive"))
      (node (ref "J1") (pin "3") (pinfunction "D+_3") (pintype "passive"))
    )
    (net (code "17") (name "/IC_UART4_RX") (class "Default")
      (node (ref "IC23") (pin "1") (pinfunction "TXD_1") (pintype "passive"))
      (node (ref "R23") (pin "2") (pinfunction "2_2") (pintype "passive"))
    )
    (net (code "18") (name "/IC_UART4_TX") (class "Default")
      (node (ref "IC23") (pin "5") (pinfunction "RXD_5") (pintype "passive"))
      (node (ref "R24") (pin "2") (pinfunction "2_2") (pintype "passive"))
    )
    (net (code "19") (name "/IC_UART_GPIO2") (class "Default")
      (node (ref "IC23") (pin "13") (pinfunction "GPIO2_13") (pintype "passive"))
      (node (ref "R60") (pin "2") (pinfunction "2_2") (pintype "passive"))
    )
    (net (code "20") (name "/IC_UART_GPIO3") (class "Default")
      (node (ref "IC23") (pin "14") (pinfunction "GPIO3_14") (pintype "passive"))
      (node (ref "R61") (pin "2") (pinfunction "2_2") (pintype "passive"))
    )
    (net (code "21") (name "/IC_UART_GPIO4") (class "Default")
      (node (ref "IC23") (pin "12") (pinfunction "GPIO4_12") (pintype "passive"))
      (node (ref "R59") (pin "2") (pinfunction "2_2") (pintype "passive"))
    )
    (net (code "22") (name "/IC_UART_GPIO5") (class "Default")
      (node (ref "IC23") (pin "8") (pinfunction "GPIO5_8") (pintype "passive"))
      (node (ref "R58") (pin "2") (pinfunction "2_2") (pintype "passive"))
    )
    (net (code "23") (name "/IC_UART_GPIO6") (class "Default")
      (node (ref "IC23") (pin "27") (pinfunction "GPIO6_27") (pintype "passive"))
      (node (ref "R56") (pin "2") (pinfunction "2_2") (pintype "passive"))
    )
    (net (code "24") (name "/IC_UART_GPIO7") (class "Default")
      (node (ref "IC23") (pin "28") (pinfunction "GPIO7_28") (pintype "passive"))
      (node (ref "R55") (pin "2") (pinfunction "2_2") (pintype "passive"))
    )
    (net (code "25") (name "/IC_UART_NCTS") (class "Default")
      (node (ref "IC23") (pin "11") (pinfunction "CTS#_11") (pintype "passive"))
      (node (ref "R25") (pin "2") (pinfunction "2_2") (pintype "passive"))
    )
    (net (code "26") (name "/IC_UART_NRTS") (class "Default")
      (node (ref "IC23") (pin "3") (pinfunction "RTS#_3") (pintype "passive"))
      (node (ref "R14") (pin "2") (pinfunction "2_2") (pintype "passive"))
    )
    (net (code "27") (name "/LED_ERROR") (class "Default")
      (node (ref "MCU") (pin "29") (pinfunction "PB10_29") (pintype "passive"))
    )
    (net (code "28") (name "/LED_MEASURING") (class "Default")
      (node (ref "MCU") (pin "28") (pinfunction "PB2_28") (pintype "passive"))
    )
    (net (code "29") (name "/LED_STATUS") (class "Default")
      (node (ref "MCU") (pin "33") (pinfunction "PB12_33") (pintype "passive"))
    )
    (net (code "30") (name "/MCU I2C1_SCL") (class "Default")
      (node (ref "MCU") (pin "58") (pinfunction "PB6_58") (pintype "passive"))
      (node (ref "R6") (pin "1") (pinfunction "1_1") (pintype "passive"))
    )
    (net (code "31") (name "/MCU I2C1_SDA") (class "Default")
      (node (ref "MCU") (pin "59") (pinfunction "PB7_59") (pintype "passive"))
      (node (ref "R4") (pin "1") (pinfunction "1_1") (pintype "passive"))
    )
    (net (code "32") (name "/MCU_BOOT") (class "Default")
      (node (ref "MCU") (pin "60") (pinfunction "BOOT0_60") (pintype "passive"))
      (node (ref "R48") (pin "1") (pinfunction "1_1") (pintype "passive"))
    )
    (net (code "33") (name "/MCU_NRST") (class "Default")
      (node (ref "C2") (pin "2") (pinfunction "2_2") (pintype "passive"))
      (node (ref "J3") (pin "10") (pinfunction "10_10") (pintype "passive"))
      (node (ref "MCU") (pin "7") (pinfunction "NRST_7") (pintype "passive"))
      (node (ref "R8") (pin "1") (pinfunction "1_1") (pintype "passive"))
      (node (ref "SW2") (pin "1") (pinfunction "1_1") (pintype "passive"))
      (node (ref "SW2") (pin "2") (pinfunction "2_2") (pintype "passive"))
    )
    (net (code "34") (name "/MCU_OSC_IN") (class "Default")
      (node (ref "C3") (pin "2") (pinfunction "2_2") (pintype "passive"))
      (node (ref "MCU") (pin "5") (pinfunction "PD0-OSC_IN_5") (pintype "passive"))
      (node (ref "Y1") (pin "1") (pinfunction "1_1") (pintype "passive"))
    )
    (net (code "35") (name "/MCU_OSC_OUT") (class "Default")
      (node (ref "C4") (pin "2") (pinfunction "2_2") (pintype "passive"))
      (node (ref "MCU") (pin "6") (pinfunction "PD1-OSC_OUT_6") (pintype "passive"))
      (node (ref "Y1") (pin "2") (pinfunction "2_2") (pintype "passive"))
    )
    (net (code "36") (name "/MCU_SWCLK") (class "Default")
      (node (ref "J3") (pin "4") (pinfunction "4_4") (pintype "passive"))
      (node (ref "MCU") (pin "49") (pinfunction "PA14_49") (pintype "passive"))
    )
    (net (code "37") (name "/MCU_SWDIO") (class "Default")
      (node (ref "J3") (pin "2") (pinfunction "2_2") (pintype "passive"))
      (node (ref "MCU") (pin "46") (pinfunction "PA13_46") (pintype "passive"))
    )
    (net (code "38") (name "/MCU_SWO") (class "Default")
      (node (ref "J3") (pin "6") (pinfunction "6_6") (pintype "passive"))
      (node (ref "MCU") (pin "55") (pinfunction "PB3_55") (pintype "passive"))
    )
    (net (code "39") (name "/MCU_UART4_RX") (class "Default")
      (node (ref "MCU") (pin "52") (pinfunction "PC11_52") (pintype "passive"))
      (node (ref "R23") (pin "1") (pinfunction "1_1") (pintype "passive"))
      (node (ref "TP17") (pin "1") (pinfunction "1_1") (pintype "passive"))
    )
    (net (code "40") (name "/MCU_UART4_TX") (class "Default")
      (node (ref "MCU") (pin "51") (pinfunction "PC10_51") (pintype "passive"))
      (node (ref "R24") (pin "1") (pinfunction "1_1") (pintype "passive"))
      (node (ref "TP18") (pin "1") (pinfunction "1_1") (pintype "passive"))
    )
    (net (code "41") (name "/MCU_UART5_RX") (class "Default")
      (node (ref "MCU") (pin "54") (pinfunction "PD2_54") (pintype "passive"))
      (node (ref "R9") (pin "2") (pinfunction "2_2") (pintype "passive"))
    )
    (net (code "42") (name "/MCU_UART5_TX") (class "Default")
      (node (ref "MCU") (pin "53") (pinfunction "PC12_53") (pintype "passive"))
      (node (ref "R10") (pin "2") (pinfunction "2_2") (pintype "passive"))
    )
    (net (code "43") (name "/MCU_UART_NCTS") (class "Default")
      (node (ref "MCU") (pin "38") (pinfunction "PC7_38") (pintype "passive"))
      (node (ref "R25") (pin "1") (pinfunction "1_1") (pintype "passive"))
    )
    (net (code "44") (name "/MCU_UART_NRTS") (class "Default")
      (node (ref "MCU") (pin "39") (pinfunction "PC8_39") (pintype "passive"))
      (node (ref "R14") (pin "1") (pinfunction "1_1") (pintype "passive"))
    )
    (net (code "45") (name "/MISO_SEN") (class "Default")
      (node (ref "J4") (pin "7") (pinfunction "7_7") (pintype "passive"))
      (node (ref "MCU") (pin "22") (pinfunction "PA6_22") (pintype "passive"))
    )
    (net (code "46") (name "/MOSI_SEN") (class "Default")
      (node (ref "J4") (pin "5") (pinfunction "5_5") (pintype "passive"))
      (node (ref "MCU") (pin "23") (pinfunction "PA7_23") (pintype "passive"))
    )
    (net (code "47") (name "/MOSI_SHREG") (class "Default")
      (node (ref "J4") (pin "10") (pinfunction "10_10") (pintype "passive"))
      (node (ref "MCU") (pin "36") (pinfunction "PB15_36") (pintype "passive"))
    )
    (net (code "48") (name "/OE") (class "Default")
      (node (ref "J4") (pin "6") (pinfunction "6_6") (pintype "passive"))
      (node (ref "MCU") (pin "24") (pinfunction "PC4_24") (pintype "passive"))
    )
    (net (code "49") (name "/RX_LED") (class "Default")
      (node (ref "IC23") (pin "23") (pinfunction "GPIO0_23") (pintype "passive"))
      (node (ref "R21") (pin "2") (pinfunction "2_2") (pintype "passive"))
    )
    (net (code "50") (name "/RX_LED_K") (class "Default")
      (node (ref "LED1") (pin "2") (pinfunction "K_2") (pintype "passive"))
      (node (ref "R21") (pin "1") (pinfunction "1_1") (pintype "passive"))
    )
    (net (code "51") (name "/SCK_SEN") (class "Default")
      (node (ref "J4") (pin "8") (pinfunction "8_8") (pintype "passive"))
      (node (ref "MCU") (pin "21") (pinfunction "PA5_21") (pintype "passive"))
    )
    (net (code "52") (name "/SCK_SHREG") (class "Default")
      (node (ref "J4") (pin "9") (pinfunction "9_9") (pintype "passive"))
      (node (ref "MCU") (pin "34") (pinfunction "PB13_34") (pintype "passive"))
    )
    (net (code "53") (name "/SCLR") (class "Default")
      (node (ref "J4") (pin "4") (pinfunction "4_4") (pintype "passive"))
      (node (ref "MCU") (pin "25") (pinfunction "PC5_25") (pintype "passive"))
    )
    (net (code "54") (name "/TX_LED") (class "Default")
      (node (ref "IC23") (pin "22") (pinfunction "GPIO1_22") (pintype "passive"))
      (node (ref "R22") (pin "2") (pinfunction "2_2") (pintype "passive"))
    )
    (net (code "55") (name "/TX_LED_K") (class "Default")
      (node (ref "LED2") (pin "2") (pinfunction "K_2") (pintype "passive"))
      (node (ref "R22") (pin "1") (pinfunction "1_1") (pintype "passive"))
    )
    (net (code "56") (name "/UART_RESET#") (class "Default")
      (node (ref "IC23") (pin "19") (pinfunction "RESET#_19") (pintype "passive"))
      (node (ref "MCU") (pin "40") (pinfunction "PC9_40") (pintype "passive"))
      (node (ref "R57") (pin "1") (pinfunction "1_1") (pintype "passive"))
    )
    (net (code "57") (name "/USB_D_N") (class "Default")
      (node (ref "IC1") (pin "6") (pinfunction "I/O1_2_6") (pintype "passive"))
      (node (ref "IC23") (pin "16") (pinfunction "USBDM_16") (pintype "passive"))
    )
    (net (code "58") (name "/USB_D_P") (class "Default")
      (node (ref "IC1") (pin "4") (pinfunction "I/O2_2_4") (pintype "passive"))
      (node (ref "IC23") (pin "15") (pinfunction "USBDP_15") (pintype "passive"))
    )
    (net (code "59") (name "/VCCD") (class "Default")
      (node (ref "C34") (pin "1") (pinfunction "1_1") (pintype "passive"))
      (node (ref "IC23") (pin "17") (pinfunction "VCCD_17") (pintype "passive"))
    )
    (net (code "60") (name "/~{S} ~{E} ~{N} ~{S} ~{O} ~{R} ~{S} ~{_} ~{E} ~{N} ~{A} ~{B} ~{L} ~{E}") (class "Default")
      (node (ref "MCU") (pin "37") (pinfunction "PC6_37") (pintype "passive"))
      (node (ref "R12") (pin "1") (pinfunction "1_1") (pintype "passive"))
      (node (ref "R13") (pin "1") (pinfunction "1_1") (pintype "passive"))
    )
    (net (code "61") (name "GND") (class "Default")
      (node (ref "Boot pin") (pin "1") (pinfunction "1_1") (pintype "passive"))
      (node (ref "C1") (pin "1") (pinfunction "1_1") (pintype "passive"))
      (node (ref "C10") (pin "1") (pinfunction "1_1") (pintype "passive"))
      (node (ref "C11") (pin "2") (pinfunction "2_2") (pintype "passive"))
      (node (ref "C12") (pin "1") (pinfunction "1_1") (pintype "passive"))
      (node (ref "C13") (pin "2") (pinfunction "-_2") (pintype "passive"))
      (node (ref "C14") (pin "1") (pinfunction "1_1") (pintype "passive"))
      (node (ref "C15") (pin "1") (pinfunction "1_1") (pintype "passive"))
      (node (ref "C16") (pin "1") (pinfunction "1_1") (pintype "passive"))
      (node (ref "C2") (pin "1") (pinfunction "1_1") (pintype "passive"))
      (node (ref "C3") (pin "1") (pinfunction "1_1") (pintype "passive"))
      (node (ref "C30") (pin "1") (pinfunction "1_1") (pintype "passive"))
      (node (ref "C31") (pin "1") (pinfunction "1_1") (pintype "passive"))
      (node (ref "C32") (pin "1") (pinfunction "1_1") (pintype "passive"))
      (node (ref "C33") (pin "1") (pinfunction "1_1") (pintype "passive"))
      (node (ref "C34") (pin "2") (pinfunction "2_2") (pintype "passive"))
      (node (ref "C35") (pin "1") (pinfunction "1_1") (pintype "passive"))
      (node (ref "C4") (pin "1") (pinfunction "1_1") (pintype "passive"))
      (node (ref "C5") (pin "1") (pinfunction "1_1") (pintype "passive"))
      (node (ref "C6") (pin "1") (pinfunction "1_1") (pintype "passive"))
      (node (ref "C7") (pin "1") (pinfunction "1_1") (pintype "passive"))
      (node (ref "C8") (pin "1") (pinfunction "1_1") (pintype "passive"))
      (node (ref "C9") (pin "1") (pinfunction "1_1") (pintype "passive"))
      (node (ref "D1") (pin "1") (pinfunction "B_1") (pintype "passive"))
      (node (ref "IC1") (pin "2") (pinfunction "GND_2") (pintype "passive"))
      (node (ref "IC23") (pin "18") (pinfunction "GND_2_18") (pintype "passive"))
      (node (ref "IC23") (pin "21") (pinfunction "GND_3_21") (pintype "passive"))
      (node (ref "IC23") (pin "7") (pinfunction "GND_1_7") (pintype "passive"))
      (node (ref "J1") (pin "5") (pinfunction "GND_5") (pintype "passive"))
      (node (ref "J2") (pin "4") (pinfunction "4_4") (pintype "passive"))
      (node (ref "J3") (pin "3") (pinfunction "3_3") (pintype "passive"))
      (node (ref "J3") (pin "5") (pinfunction "5_5") (pintype "passive"))
      (node (ref "J4") (pin "2") (pinfunction "2_2") (pintype "passive"))
      (node (ref "MCU") (pin "12") (pinfunction "VSSA_12") (pintype "passive"))
      (node (ref "MCU") (pin "18") (pinfunction "VSS_4_18") (pintype "passive"))
      (node (ref "MCU") (pin "31") (pinfunction "VSS_1_31") (pintype "passive"))
      (node (ref "MCU") (pin "47") (pinfunction "VSS_2_47") (pintype "passive"))
      (node (ref "MCU") (pin "63") (pinfunction "VSS_3_63") (pintype "passive"))
      (node (ref "SW1") (pin "1") (pinfunction "1_1") (pintype "passive"))
      (node (ref "SW1") (pin "2") (pinfunction "2_2") (pintype "passive"))
      (node (ref "SW2") (pin "3") (pinfunction "3_3") (pintype "passive"))
      (node (ref "SW2") (pin "4") (pinfunction "4_4") (pintype "passive"))
      (node (ref "TP4") (pin "1") (pinfunction "1_1") (pintype "passive"))
      (node (ref "TP6") (pin "1") (pinfunction "1_1") (pintype "passive"))
      (node (ref "U1") (pin "4") (pinfunction "TAB_4") (pintype "passive"))
      (node (ref "UART5") (pin "1") (pinfunction "1_1") (pintype "passive"))
    )
    (net (code "62") (name "Net-(Boot pin-Pad2)") (class "Default")
      (node (ref "Boot pin") (pin "2") (pinfunction "2_2") (pintype "passive"))
      (node (ref "R7") (pin "2") (pinfunction "2_2") (pintype "passive"))
    )
    (net (code "63") (name "Net-(Q1-G)") (class "Default")
      (node (ref "Q1") (pin "1") (pinfunction "G_1") (pintype "passive"))
      (node (ref "R12") (pin "2") (pinfunction "2_2") (pintype "passive"))
    )
    (net (code "64") (name "Net-(R13-Pad2)") (class "Default")
      (node (ref "R13") (pin "2") (pinfunction "2_2") (pintype "passive"))
      (node (ref "R20") (pin "1") (pinfunction "1_1") (pintype "passive"))
    )
    (net (code "65") (name "Net-(R48-Pad2)") (class "Default")
      (node (ref "R48") (pin "2") (pinfunction "2_2") (pintype "passive"))
      (node (ref "R7") (pin "1") (pinfunction "1_1") (pintype "passive"))
    )
    (net (code "66") (name "VBUS") (class "Default")
      (node (ref "C32") (pin "2") (pinfunction "2_2") (pintype "passive"))
      (node (ref "FB1") (pin "2") (pinfunction "2_2") (pintype "passive"))
      (node (ref "IC1") (pin "5") (pinfunction "VBUS_5") (pintype "passive"))
      (node (ref "J1") (pin "1") (pinfunction "VBUS_1") (pintype "passive"))
    )
    (net (code "67") (name "unconnected-(IC23-DCD#-Pad10)") (class "Default")
      (node (ref "IC23") (pin "10") (pinfunction "DCD#_10") (pintype "passive+no_connect"))
    )
    (net (code "68") (name "unconnected-(IC23-DNU-Pad26)") (class "Default")
      (node (ref "IC23") (pin "26") (pinfunction "DNU_26") (pintype "passive+no_connect"))
    )
    (net (code "69") (name "unconnected-(IC23-DSR#-Pad9)") (class "Default")
      (node (ref "IC23") (pin "9") (pinfunction "DSR#_9") (pintype "passive+no_connect"))
    )
    (net (code "70") (name "unconnected-(IC23-DTR#-Pad2)") (class "Default")
      (node (ref "IC23") (pin "2") (pinfunction "DTR#_2") (pintype "passive+no_connect"))
    )
    (net (code "71") (name "unconnected-(IC23-NC_1-Pad24)") (class "Default")
      (node (ref "IC23") (pin "24") (pinfunction "NC_1_24") (pintype "passive+no_connect"))
    )
    (net (code "72") (name "unconnected-(IC23-NC_2-Pad25)") (class "Default")
      (node (ref "IC23") (pin "25") (pinfunction "NC_2_25") (pintype "passive+no_connect"))
    )
    (net (code "73") (name "unconnected-(IC23-RI#-Pad6)") (class "Default")
      (node (ref "IC23") (pin "6") (pinfunction "RI#_6") (pintype "passive+no_connect"))
    )
    (net (code "74") (name "unconnected-(J1-ID-Pad4)") (class "Default")
      (node (ref "J1") (pin "4") (pinfunction "ID_4") (pintype "passive"))
    )
    (net (code "75") (name "unconnected-(J3-Pad7)") (class "Default")
      (node (ref "J3") (pin "7") (pinfunction "7_7") (pintype "passive+no_connect"))
    )
    (net (code "76") (name "unconnected-(J3-Pad8)") (class "Default")
      (node (ref "J3") (pin "8") (pinfunction "8_8") (pintype "passive+no_connect"))
    )
    (net (code "77") (name "unconnected-(J3-Pad9)") (class "Default")
      (node (ref "J3") (pin "9") (pinfunction "9_9") (pintype "passive+no_connect"))
    )
    (net (code "78") (name "unconnected-(J4-Pad3)") (class "Default")
      (node (ref "J4") (pin "3") (pinfunction "3_3") (pintype "passive"))
    )
    (net (code "79") (name "unconnected-(MCU-PA0-WKUP-Pad14)") (class "Default")
      (node (ref "MCU") (pin "14") (pinfunction "PA0-WKUP_14") (pintype "passive+no_connect"))
    )
    (net (code "80") (name "unconnected-(MCU-PA1-Pad15)") (class "Default")
      (node (ref "MCU") (pin "15") (pinfunction "PA1_15") (pintype "passive+no_connect"))
    )
    (net (code "81") (name "unconnected-(MCU-PA2-Pad16)") (class "Default")
      (node (ref "MCU") (pin "16") (pinfunction "PA2_16") (pintype "passive"))
    )
    (net (code "82") (name "unconnected-(MCU-PA3-Pad17)") (class "Default")
      (node (ref "MCU") (pin "17") (pinfunction "PA3_17") (pintype "passive+no_connect"))
    )
    (net (code "83") (name "unconnected-(MCU-PA4-Pad20)") (class "Default")
      (node (ref "MCU") (pin "20") (pinfunction "PA4_20") (pintype "passive+no_connect"))
    )
    (net (code "84") (name "unconnected-(MCU-PA8-Pad41)") (class "Default")
      (node (ref "MCU") (pin "41") (pinfunction "PA8_41") (pintype "passive+no_connect"))
    )
    (net (code "85") (name "unconnected-(MCU-PA9-Pad42)") (class "Default")
      (node (ref "MCU") (pin "42") (pinfunction "PA9_42") (pintype "passive+no_connect"))
    )
    (net (code "86") (name "unconnected-(MCU-PA10-Pad43)") (class "Default")
      (node (ref "MCU") (pin "43") (pinfunction "PA10_43") (pintype "passive+no_connect"))
    )
    (net (code "87") (name "unconnected-(MCU-PA11-Pad44)") (class "Default")
      (node (ref "MCU") (pin "44") (pinfunction "PA11_44") (pintype "passive+no_connect"))
    )
    (net (code "88") (name "unconnected-(MCU-PA12-Pad45)") (class "Default")
      (node (ref "MCU") (pin "45") (pinfunction "PA12_45") (pintype "passive+no_connect"))
    )
    (net (code "89") (name "unconnected-(MCU-PA15-Pad50)") (class "Default")
      (node (ref "MCU") (pin "50") (pinfunction "PA15_50") (pintype "passive+no_connect"))
    )
    (net (code "90") (name "unconnected-(MCU-PB0-Pad26)") (class "Default")
      (node (ref "MCU") (pin "26") (pinfunction "PB0_26") (pintype "passive"))
    )
    (net (code "91") (name "unconnected-(MCU-PB1-Pad27)") (class "Default")
      (node (ref "MCU") (pin "27") (pinfunction "PB1_27") (pintype "passive"))
    )
    (net (code "92") (name "unconnected-(MCU-PB4-Pad56)") (class "Default")
      (node (ref "MCU") (pin "56") (pinfunction "PB4_56") (pintype "passive+no_connect"))
    )
    (net (code "93") (name "unconnected-(MCU-PB5-Pad57)") (class "Default")
      (node (ref "MCU") (pin "57") (pinfunction "PB5_57") (pintype "passive+no_connect"))
    )
    (net (code "94") (name "unconnected-(MCU-PB11-Pad30)") (class "Default")
      (node (ref "MCU") (pin "30") (pinfunction "PB11_30") (pintype "passive+no_connect"))
    )
    (net (code "95") (name "unconnected-(MCU-PB14-Pad35)") (class "Default")
      (node (ref "MCU") (pin "35") (pinfunction "PB14_35") (pintype "passive"))
    )
    (net (code "96") (name "unconnected-(MCU-PC0-Pad8)") (class "Default")
      (node (ref "MCU") (pin "8") (pinfunction "PC0_8") (pintype "passive+no_connect"))
    )
    (net (code "97") (name "unconnected-(MCU-PC1-Pad9)") (class "Default")
      (node (ref "MCU") (pin "9") (pinfunction "PC1_9") (pintype "passive+no_connect"))
    )
    (net (code "98") (name "unconnected-(MCU-PC2-Pad10)") (class "Default")
      (node (ref "MCU") (pin "10") (pinfunction "PC2_10") (pintype "passive+no_connect"))
    )
    (net (code "99") (name "unconnected-(MCU-PC3-Pad11)") (class "Default")
      (node (ref "MCU") (pin "11") (pinfunction "PC3_11") (pintype "passive+no_connect"))
    )
    (net (code "100") (name "unconnected-(MCU-PC6-Pad37)") (class "Default")
      (node (ref "MCU") (pin "37") (pinfunction "PC6_37") (pintype "passive"))
    )
    (net (code "101") (name "unconnected-(MCU-PC13-TAMPER-RTC-Pad2)") (class "Default")
      (node (ref "MCU") (pin "2") (pinfunction "PC13-TAMPER-RTC_2") (pintype "passive+no_connect"))
    )
    (net (code "102") (name "unconnected-(MCU-PC14-_OSC32_IN-Pad3)") (class "Default")
      (node (ref "MCU") (pin "3") (pinfunction "PC14-_OSC32_IN_3") (pintype "passive+no_connect"))
    )
    (net (code "103") (name "unconnected-(MCU-PC15-_OSC32_OUT-Pad4)") (class "Default")
      (node (ref "MCU") (pin "4") (pinfunction "PC15-_OSC32_OUT_4") (pintype "passive+no_connect"))
    )
  )
)
